# Tastereinheit.net
KiCad netlist of a schematic drawn in EAGLE
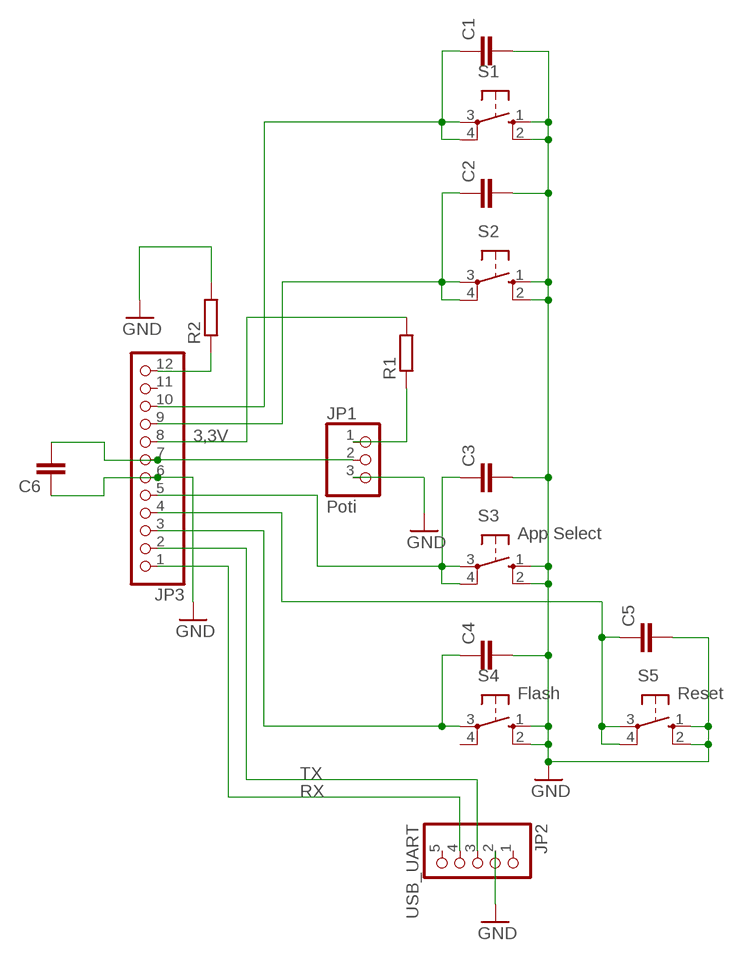
[diagram p0: schematic, sheet 1]

(export (version "E")
  (design (tool "Eeschema 10.0.6"))
  (components
    (comp (ref "C1")
      (value "C-EUC0805")
      (footprint "eagle-import:C0805")
      (libsource (lib "eagle-import") (part "C-EUC0805"))
    )
    (comp (ref "C2")
      (value "C-EUC0805")
      (footprint "eagle-import:C0805")
      (libsource (lib "eagle-import") (part "C-EUC0805"))
    )
    (comp (ref "C3")
      (value "C-EUC0805")
      (footprint "eagle-import:C0805")
      (libsource (lib "eagle-import") (part "C-EUC0805"))
    )
    (comp (ref "C4")
      (value "C-EUC0805")
      (footprint "eagle-import:C0805")
      (libsource (lib "eagle-import") (part "C-EUC0805"))
    )
    (comp (ref "C5")
      (value "C-EUC0805")
      (footprint "eagle-import:C0805")
      (libsource (lib "eagle-import") (part "C-EUC0805"))
    )
    (comp (ref "C6")
      (value "C-EUC0805")
      (footprint "eagle-import:C0805")
      (libsource (lib "eagle-import") (part "C-EUC0805"))
    )
    (comp (ref "JP1")
      (value "Poti")
      (footprint "eagle-import:1X03_90")
      (libsource (lib "eagle-import") (part "PINHD-1X3/90"))
    )
    (comp (ref "JP2")
      (value "USB_UART")
      (footprint "eagle-import:1X05_90")
      (libsource (lib "eagle-import") (part "PINHD-1X5/90"))
    )
    (comp (ref "JP3")
      (value "PINHD-1X12/90")
      (footprint "eagle-import:1X12_90")
      (libsource (lib "eagle-import") (part "PINHD-1X12/90"))
    )
    (comp (ref "R1")
      (value "R-EU_R0805")
      (footprint "eagle-import:R0805")
      (libsource (lib "eagle-import") (part "R-EU_R0805"))
    )
    (comp (ref "R2")
      (value "R-EU_R0805")
      (footprint "eagle-import:R0805")
      (libsource (lib "eagle-import") (part "R-EU_R0805"))
    )
    (comp (ref "S1")
      (value "10-XX")
      (footprint "eagle-import:B3F-10XX")
      (fields (field (name "MPN") "B3F-1000"))
      (libsource (lib "eagle-import") (part "10-XX"))
    )
    (comp (ref "S2")
      (value "10-XX")
      (footprint "eagle-import:B3F-10XX")
      (fields (field (name "MPN") "B3F-1000"))
      (libsource (lib "eagle-import") (part "10-XX"))
    )
    (comp (ref "S3")
      (value "App Select")
      (footprint "eagle-import:B3F-10XX")
      (fields (field (name "MPN") "B3F-1000"))
      (libsource (lib "eagle-import") (part "10-XX"))
    )
    (comp (ref "S4")
      (value "Flash")
      (footprint "eagle-import:B3F-10XX")
      (fields (field (name "MPN") "B3F-1000"))
      (libsource (lib "eagle-import") (part "10-XX"))
    )
    (comp (ref "S5")
      (value "Reset")
      (footprint "eagle-import:B3F-10XX")
      (fields (field (name "MPN") "B3F-1000"))
      (libsource (lib "eagle-import") (part "10-XX"))
    )
  )
  (nets
    (net (code "1") (name "/3,3V") (class "Default")
      (node (ref "JP3") (pin "8") (pinfunction "8_8") (pintype "passive"))
      (node (ref "R1") (pin "2") (pinfunction "2_2") (pintype "passive"))
    )
    (net (code "2") (name "/RX") (class "Default")
      (node (ref "JP2") (pin "4") (pinfunction "4_4") (pintype "passive"))
      (node (ref "JP3") (pin "1") (pinfunction "1_1") (pintype "passive"))
    )
    (net (code "3") (name "/TX") (class "Default")
      (node (ref "JP2") (pin "3") (pinfunction "3_3") (pintype "passive"))
      (node (ref "JP3") (pin "2") (pinfunction "2_2") (pintype "passive"))
    )
    (net (code "4") (name "GND") (class "Default")
      (node (ref "C1") (pin "2") (pinfunction "2_2") (pintype "passive"))
      (node (ref "C2") (pin "2") (pinfunction "2_2") (pintype "passive"))
      (node (ref "C3") (pin "2") (pinfunction "2_2") (pintype "passive"))
      (node (ref "C4") (pin "2") (pinfunction "2_2") (pintype "passive"))
      (node (ref "C5") (pin "2") (pinfunction "2_2") (pintype "passive"))
      (node (ref "C6") (pin "1") (pinfunction "1_1") (pintype "passive"))
      (node (ref "JP1") (pin "3") (pinfunction "3_3") (pintype "passive"))
      (node (ref "JP2") (pin "2") (pinfunction "2_2") (pintype "passive"))
      (node (ref "JP3") (pin "6") (pinfunction "6_6") (pintype "passive"))
      (node (ref "R2") (pin "2") (pinfunction "2_2") (pintype "passive"))
      (node (ref "S1") (pin "1") (pinfunction "S_1") (pintype "passive"))
      (node (ref "S1") (pin "2") (pinfunction "S1_2") (pintype "passive"))
      (node (ref "S2") (pin "1") (pinfunction "S_1") (pintype "passive"))
      (node (ref "S2") (pin "2") (pinfunction "S1_2") (pintype "passive"))
      (node (ref "S3") (pin "1") (pinfunction "S_1") (pintype "passive"))
      (node (ref "S3") (pin "2") (pinfunction "S1_2") (pintype "passive"))
      (node (ref "S4") (pin "1") (pinfunction "S_1") (pintype "passive"))
      (node (ref "S4") (pin "2") (pinfunction "S1_2") (pintype "passive"))
      (node (ref "S5") (pin "1") (pinfunction "S_1") (pintype "passive"))
      (node (ref "S5") (pin "2") (pinfunction "S1_2") (pintype "passive"))
    )
    (net (code "5") (name "Net-(C6-Pad2)") (class "Default")
      (node (ref "C6") (pin "2") (pinfunction "2_2") (pintype "passive"))
      (node (ref "JP1") (pin "2") (pinfunction "2_2") (pintype "passive"))
      (node (ref "JP3") (pin "7") (pinfunction "7_7") (pintype "passive"))
    )
    (net (code "6") (name "Net-(JP1-Pad1)") (class "Default")
      (node (ref "JP1") (pin "1") (pinfunction "1_1") (pintype "passive"))
      (node (ref "R1") (pin "1") (pinfunction "1_1") (pintype "passive"))
    )
    (net (code "7") (name "Net-(JP3-Pad12)") (class "Default")
      (node (ref "JP3") (pin "12") (pinfunction "12_12") (pintype "passive"))
      (node (ref "R2") (pin "1") (pinfunction "1_1") (pintype "passive"))
    )
    (net (code "8") (name "Net-(S1-P)") (class "Default")
      (node (ref "C1") (pin "1") (pinfunction "1_1") (pintype "passive"))
      (node (ref "JP3") (pin "10") (pinfunction "10_10") (pintype "passive"))
      (node (ref "S1") (pin "3") (pinfunction "P_3") (pintype "passive"))
      (node (ref "S1") (pin "4") (pinfunction "P1_4") (pintype "passive"))
    )
    (net (code "9") (name "Net-(S2-P)") (class "Default")
      (node (ref "C2") (pin "1") (pinfunction "1_1") (pintype "passive"))
      (node (ref "JP3") (pin "9") (pinfunction "9_9") (pintype "passive"))
      (node (ref "S2") (pin "3") (pinfunction "P_3") (pintype "passive"))
      (node (ref "S2") (pin "4") (pinfunction "P1_4") (pintype "passive"))
    )
    (net (code "10") (name "Net-(S3-P)") (class "Default")
      (node (ref "C3") (pin "1") (pinfunction "1_1") (pintype "passive"))
      (node (ref "JP3") (pin "5") (pinfunction "5_5") (pintype "passive"))
      (node (ref "S3") (pin "3") (pinfunction "P_3") (pintype "passive"))
      (node (ref "S3") (pin "4") (pinfunction "P1_4") (pintype "passive"))
    )
    (net (code "11") (name "Net-(S4-P)") (class "Default")
      (node (ref "C4") (pin "1") (pinfunction "1_1") (pintype "passive"))
      (node (ref "JP3") (pin "3") (pinfunction "3_3") (pintype "passive"))
      (node (ref "S4") (pin "3") (pinfunction "P_3") (pintype "passive"))
    )
    (net (code "12") (name "Net-(S5-P)") (class "Default")
      (node (ref "C5") (pin "1") (pinfunction "1_1") (pintype "passive"))
      (node (ref "JP3") (pin "4") (pinfunction "4_4") (pintype "passive"))
      (node (ref "S5") (pin "3") (pinfunction "P_3") (pintype "passive"))
      (node (ref "S5") (pin "4") (pinfunction "P1_4") (pintype "passive"))
    )
    (net (code "13") (name "unconnected-(JP2-Pad1)") (class "Default")
      (node (ref "JP2") (pin "1") (pinfunction "1_1") (pintype "passive"))
    )
    (net (code "14") (name "unconnected-(JP2-Pad5)") (class "Default")
      (node (ref "JP2") (pin "5") (pinfunction "5_5") (pintype "passive"))
    )
    (net (code "15") (name "unconnected-(JP3-Pad11)") (class "Default")
      (node (ref "JP3") (pin "11") (pinfunction "11_11") (pintype "passive"))
    )
    (net (code "16") (name "unconnected-(S4-P1-Pad4)") (class "Default")
      (node (ref "S4") (pin "4") (pinfunction "P1_4") (pintype "passive"))
    )
  )
)
